# equalize_1.net
KiCad netlist of a schematic drawn in EAGLE
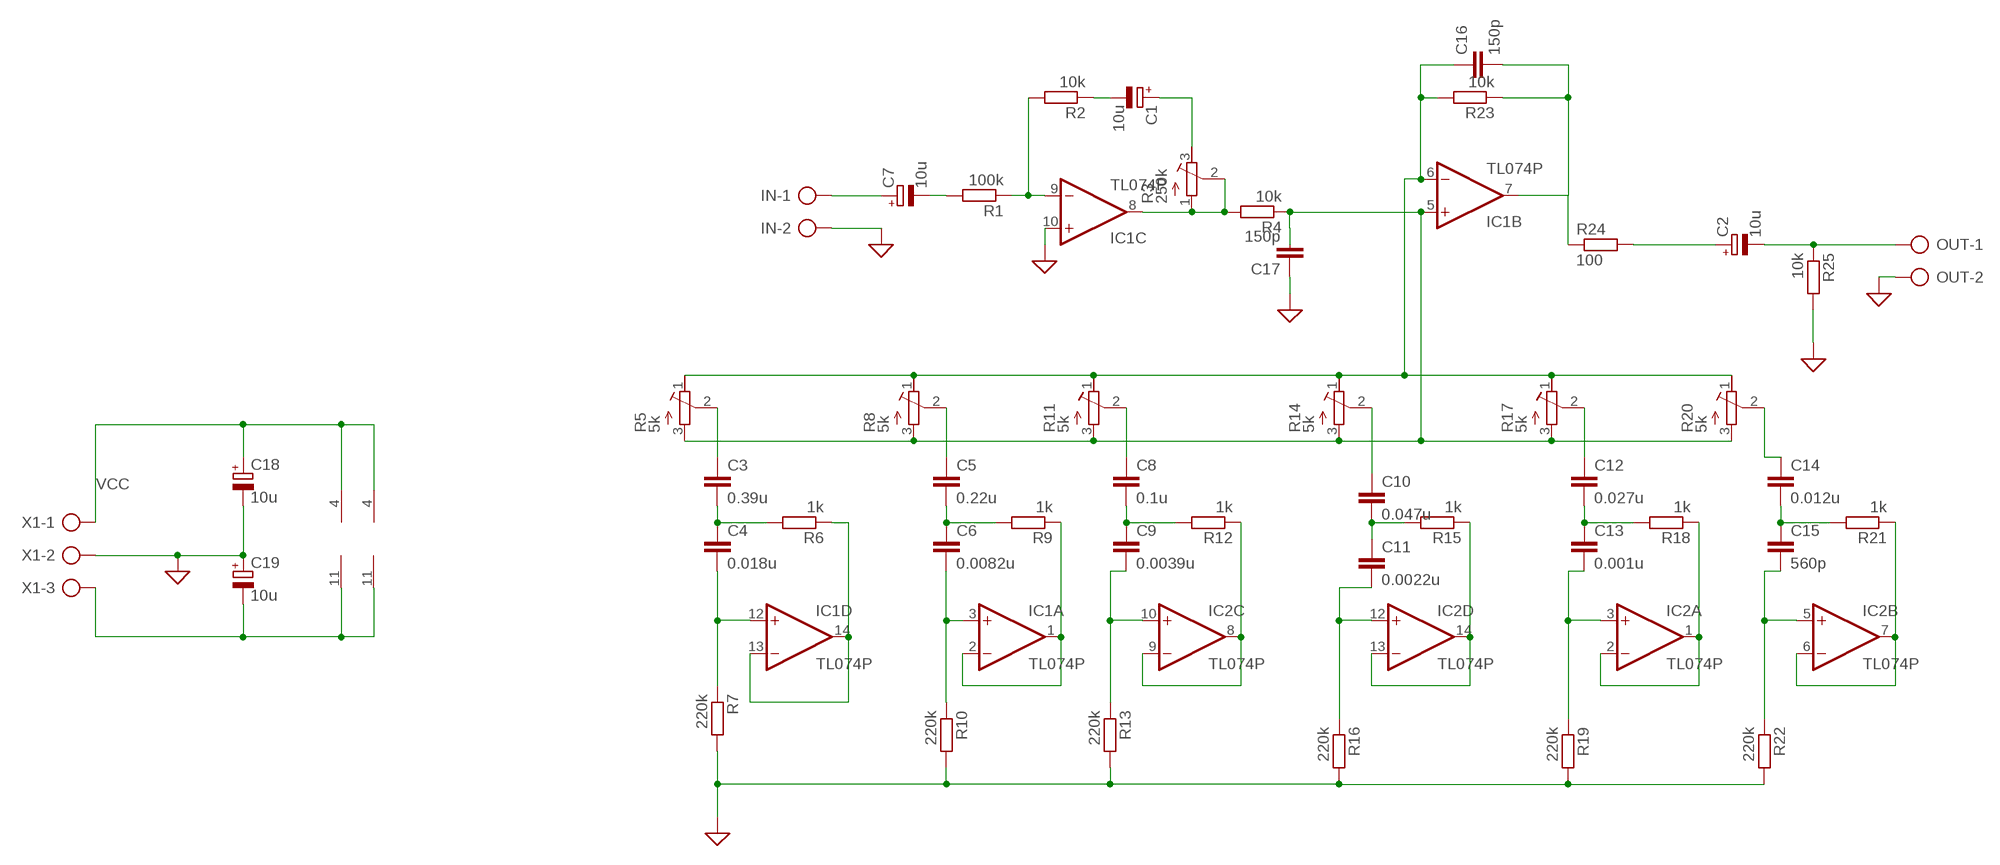
[diagram p0: schematic, sheet 1]

(export (version "E")
  (design (tool "Eeschema 10.0.6"))
  (components
    (comp (ref "C1")
      (value "10u")
      (footprint "eagle-import:E2,5-5")
      (libsource (lib "eagle-import") (part "CPOL-EUE2.5-5"))
    )
    (comp (ref "C2")
      (value "10u")
      (footprint "eagle-import:E2,5-5")
      (libsource (lib "eagle-import") (part "CPOL-EUE2.5-5"))
    )
    (comp (ref "C3")
      (value "0.39u")
      (footprint "eagle-import:C0603")
      (libsource (lib "eagle-import") (part "C-EUC0603"))
    )
    (comp (ref "C4")
      (value "0.018u")
      (footprint "eagle-import:C0603")
      (libsource (lib "eagle-import") (part "C-EUC0603"))
    )
    (comp (ref "C5")
      (value "0.22u")
      (footprint "eagle-import:C0603")
      (libsource (lib "eagle-import") (part "C-EUC0603"))
    )
    (comp (ref "C6")
      (value "0.0082u")
      (footprint "eagle-import:C0603")
      (libsource (lib "eagle-import") (part "C-EUC0603"))
    )
    (comp (ref "C7")
      (value "10u")
      (footprint "eagle-import:E2,5-5")
      (libsource (lib "eagle-import") (part "CPOL-EUE2.5-5"))
    )
    (comp (ref "C8")
      (value "0.1u")
      (footprint "eagle-import:C0603")
      (libsource (lib "eagle-import") (part "C-EUC0603"))
    )
    (comp (ref "C9")
      (value "0.0039u")
      (footprint "eagle-import:C0603")
      (libsource (lib "eagle-import") (part "C-EUC0603"))
    )
    (comp (ref "C10")
      (value "0.047u")
      (footprint "eagle-import:C0603")
      (libsource (lib "eagle-import") (part "C-EUC0603"))
    )
    (comp (ref "C11")
      (value "0.0022u")
      (footprint "eagle-import:C0603")
      (libsource (lib "eagle-import") (part "C-EUC0603"))
    )
    (comp (ref "C12")
      (value "0.027u")
      (footprint "eagle-import:C0603")
      (libsource (lib "eagle-import") (part "C-EUC0603"))
    )
    (comp (ref "C13")
      (value "0.001u")
      (footprint "eagle-import:C0603")
      (libsource (lib "eagle-import") (part "C-EUC0603"))
    )
    (comp (ref "C14")
      (value "0.012u")
      (footprint "eagle-import:C0603")
      (libsource (lib "eagle-import") (part "C-EUC0603"))
    )
    (comp (ref "C15")
      (value "560p")
      (footprint "eagle-import:C0603")
      (libsource (lib "eagle-import") (part "C-EUC0603"))
    )
    (comp (ref "C16")
      (value "150p")
      (footprint "eagle-import:C0603")
      (libsource (lib "eagle-import") (part "C-EUC0603"))
    )
    (comp (ref "C17")
      (value "150p")
      (footprint "eagle-import:C0603")
      (libsource (lib "eagle-import") (part "C-EUC0603"))
    )
    (comp (ref "C18")
      (value "10u")
      (footprint "eagle-import:E2,5-5")
      (libsource (lib "eagle-import") (part "CPOL-EUE2.5-5"))
    )
    (comp (ref "C19")
      (value "10u")
      (footprint "eagle-import:E2,5-5")
      (libsource (lib "eagle-import") (part "CPOL-EUE2.5-5"))
    )
    (comp (ref "IC1")
      (value "TL074P")
      (footprint "eagle-import:DIL14")
      (libsource (lib "eagle-import") (part "TL074P"))
    )
    (comp (ref "IC2")
      (value "TL074P")
      (footprint "eagle-import:DIL14")
      (libsource (lib "eagle-import") (part "TL074P"))
    )
    (comp (ref "IN")
      (value "AK500/2")
      (footprint "eagle-import:AK500_2")
      (libsource (lib "eagle-import") (part "AK500/2"))
    )
    (comp (ref "OUT")
      (value "AK500/2")
      (footprint "eagle-import:AK500_2")
      (libsource (lib "eagle-import") (part "AK500/2"))
    )
    (comp (ref "R1")
      (value "100k")
      (footprint "eagle-import:0207_7")
      (libsource (lib "eagle-import") (part "R-EU_0207/7"))
    )
    (comp (ref "R2")
      (value "10k")
      (footprint "eagle-import:0207_7")
      (libsource (lib "eagle-import") (part "R-EU_0207/7"))
    )
    (comp (ref "R3")
      (value "250k")
      (footprint "eagle-import:RTRIM3339P")
      (libsource (lib "eagle-import") (part "R-TRIMM3339P"))
    )
    (comp (ref "R4")
      (value "10k")
      (footprint "eagle-import:0207_7")
      (libsource (lib "eagle-import") (part "R-EU_0207/7"))
    )
    (comp (ref "R5")
      (value "5k")
      (footprint "eagle-import:RTRIMT93YA")
      (libsource (lib "eagle-import") (part "resistor_R-TRIMMT93YA"))
    )
    (comp (ref "R6")
      (value "1k")
      (footprint "eagle-import:0207_7")
      (libsource (lib "eagle-import") (part "R-EU_0207/7"))
    )
    (comp (ref "R7")
      (value "220k")
      (footprint "eagle-import:0207_7")
      (libsource (lib "eagle-import") (part "R-EU_0207/7"))
    )
    (comp (ref "R8")
      (value "5k")
      (footprint "eagle-import:RTRIMT93YA")
      (libsource (lib "eagle-import") (part "resistor_R-TRIMMT93YA"))
    )
    (comp (ref "R9")
      (value "1k")
      (footprint "eagle-import:0207_7")
      (libsource (lib "eagle-import") (part "R-EU_0207/7"))
    )
    (comp (ref "R10")
      (value "220k")
      (footprint "eagle-import:0207_7")
      (libsource (lib "eagle-import") (part "R-EU_0207/7"))
    )
    (comp (ref "R11")
      (value "5k")
      (footprint "eagle-import:RTRIMT93YA")
      (libsource (lib "eagle-import") (part "resistor_R-TRIMMT93YA"))
    )
    (comp (ref "R12")
      (value "1k")
      (footprint "eagle-import:0207_7")
      (libsource (lib "eagle-import") (part "R-EU_0207/7"))
    )
    (comp (ref "R13")
      (value "220k")
      (footprint "eagle-import:0207_7")
      (libsource (lib "eagle-import") (part "R-EU_0207/7"))
    )
    (comp (ref "R14")
      (value "5k")
      (footprint "eagle-import:RTRIMT93YA")
      (libsource (lib "eagle-import") (part "resistor_R-TRIMMT93YA"))
    )
    (comp (ref "R15")
      (value "1k")
      (footprint "eagle-import:0207_7")
      (libsource (lib "eagle-import") (part "R-EU_0207/7"))
    )
    (comp (ref "R16")
      (value "220k")
      (footprint "eagle-import:0207_7")
      (libsource (lib "eagle-import") (part "R-EU_0207/7"))
    )
    (comp (ref "R17")
      (value "5k")
      (footprint "eagle-import:RTRIMT93YA")
      (libsource (lib "eagle-import") (part "resistor_R-TRIMMT93YA"))
    )
    (comp (ref "R18")
      (value "1k")
      (footprint "eagle-import:0207_7")
      (libsource (lib "eagle-import") (part "R-EU_0207/7"))
    )
    (comp (ref "R19")
      (value "220k")
      (footprint "eagle-import:0207_7")
      (libsource (lib "eagle-import") (part "R-EU_0207/7"))
    )
    (comp (ref "R20")
      (value "5k")
      (footprint "eagle-import:RTRIMT93YA")
      (libsource (lib "eagle-import") (part "resistor_R-TRIMMT93YA"))
    )
    (comp (ref "R21")
      (value "1k")
      (footprint "eagle-import:0207_7")
      (libsource (lib "eagle-import") (part "R-EU_0207/7"))
    )
    (comp (ref "R22")
      (value "220k")
      (footprint "eagle-import:0207_7")
      (libsource (lib "eagle-import") (part "R-EU_0207/7"))
    )
    (comp (ref "R23")
      (value "10k")
      (footprint "eagle-import:0207_7")
      (libsource (lib "eagle-import") (part "R-EU_0207/7"))
    )
    (comp (ref "R24")
      (value "100")
      (footprint "eagle-import:0207_7")
      (libsource (lib "eagle-import") (part "R-EU_0207/7"))
    )
    (comp (ref "R25")
      (value "10k")
      (footprint "eagle-import:0207_7")
      (libsource (lib "eagle-import") (part "R-EU_0207/7"))
    )
    (comp (ref "X1")
      (value "AK500/3")
      (footprint "eagle-import:AK500_3")
      (libsource (lib "eagle-import") (part "AK500/3"))
    )
  )
  (nets
    (net (code "1") (name "/VCC") (class "Default")
      (node (ref "C18") (pin "+") (pinfunction "+_+") (pintype "passive"))
      (node (ref "IC1") (pin "4") (pinfunction "V+_4") (pintype "power_in"))
      (node (ref "IC2") (pin "4") (pinfunction "V+_4") (pintype "power_in"))
      (node (ref "X1") (pin "1") (pinfunction "KL_1") (pintype "passive"))
    )
    (net (code "2") (name "Net-(C1-Pad-)") (class "Default")
      (node (ref "C1") (pin "-") (pinfunction "-_-") (pintype "passive"))
      (node (ref "R2") (pin "1") (pinfunction "1_1") (pintype "passive"))
    )
    (net (code "3") (name "Net-(C2-Pad+)") (class "Default")
      (node (ref "C2") (pin "+") (pinfunction "+_+") (pintype "passive"))
      (node (ref "R24") (pin "2") (pinfunction "2_2") (pintype "passive"))
    )
    (net (code "4") (name "Net-(C3-Pad2)") (class "Default")
      (node (ref "C3") (pin "2") (pinfunction "2_2") (pintype "passive"))
      (node (ref "C4") (pin "1") (pinfunction "1_1") (pintype "passive"))
      (node (ref "R6") (pin "2") (pinfunction "2_2") (pintype "passive"))
    )
    (net (code "5") (name "Net-(C5-Pad2)") (class "Default")
      (node (ref "C5") (pin "2") (pinfunction "2_2") (pintype "passive"))
      (node (ref "C6") (pin "1") (pinfunction "1_1") (pintype "passive"))
      (node (ref "R9") (pin "2") (pinfunction "2_2") (pintype "passive"))
    )
    (net (code "6") (name "Net-(C7-Pad-)") (class "Default")
      (node (ref "C7") (pin "-") (pinfunction "-_-") (pintype "passive"))
      (node (ref "R1") (pin "2") (pinfunction "2_2") (pintype "passive"))
    )
    (net (code "7") (name "Net-(C8-Pad2)") (class "Default")
      (node (ref "C8") (pin "2") (pinfunction "2_2") (pintype "passive"))
      (node (ref "C9") (pin "1") (pinfunction "1_1") (pintype "passive"))
      (node (ref "R12") (pin "2") (pinfunction "2_2") (pintype "passive"))
    )
    (net (code "8") (name "Net-(C10-Pad2)") (class "Default")
      (node (ref "C10") (pin "2") (pinfunction "2_2") (pintype "passive"))
      (node (ref "C11") (pin "1") (pinfunction "1_1") (pintype "passive"))
      (node (ref "R15") (pin "2") (pinfunction "2_2") (pintype "passive"))
    )
    (net (code "9") (name "Net-(C12-Pad2)") (class "Default")
      (node (ref "C12") (pin "2") (pinfunction "2_2") (pintype "passive"))
      (node (ref "C13") (pin "1") (pinfunction "1_1") (pintype "passive"))
      (node (ref "R18") (pin "2") (pinfunction "2_2") (pintype "passive"))
    )
    (net (code "10") (name "Net-(C14-Pad2)") (class "Default")
      (node (ref "C14") (pin "2") (pinfunction "2_2") (pintype "passive"))
      (node (ref "C15") (pin "1") (pinfunction "1_1") (pintype "passive"))
      (node (ref "R21") (pin "2") (pinfunction "2_2") (pintype "passive"))
    )
    (net (code "11") (name "Net-(IC1A-+IN)") (class "Default")
      (node (ref "C6") (pin "2") (pinfunction "2_2") (pintype "passive"))
      (node (ref "IC1") (pin "3") (pinfunction "+IN_3") (pintype "input"))
      (node (ref "R10") (pin "1") (pinfunction "1_1") (pintype "passive"))
    )
    (net (code "12") (name "Net-(IC1A--IN)") (class "Default")
      (node (ref "IC1") (pin "1") (pinfunction "OUT_1") (pintype "output"))
      (node (ref "IC1") (pin "2") (pinfunction "-IN_2") (pintype "input"))
      (node (ref "R9") (pin "1") (pinfunction "1_1") (pintype "passive"))
    )
    (net (code "13") (name "Net-(IC1B-+IN)") (class "Default")
      (node (ref "C17") (pin "2") (pinfunction "2_2") (pintype "passive"))
      (node (ref "IC1") (pin "5") (pinfunction "+IN_5") (pintype "input"))
      (node (ref "R11") (pin "3") (pinfunction "A_3") (pintype "passive"))
      (node (ref "R14") (pin "3") (pinfunction "A_3") (pintype "passive"))
      (node (ref "R17") (pin "3") (pinfunction "A_3") (pintype "passive"))
      (node (ref "R20") (pin "3") (pinfunction "A_3") (pintype "passive"))
      (node (ref "R4") (pin "1") (pinfunction "1_1") (pintype "passive"))
      (node (ref "R5") (pin "3") (pinfunction "A_3") (pintype "passive"))
      (node (ref "R8") (pin "3") (pinfunction "A_3") (pintype "passive"))
    )
    (net (code "14") (name "Net-(IC1B--IN)") (class "Default")
      (node (ref "C16") (pin "1") (pinfunction "1_1") (pintype "passive"))
      (node (ref "IC1") (pin "6") (pinfunction "-IN_6") (pintype "input"))
      (node (ref "R11") (pin "1") (pinfunction "E_1") (pintype "passive"))
      (node (ref "R14") (pin "1") (pinfunction "E_1") (pintype "passive"))
      (node (ref "R17") (pin "1") (pinfunction "E_1") (pintype "passive"))
      (node (ref "R20") (pin "1") (pinfunction "E_1") (pintype "passive"))
      (node (ref "R23") (pin "2") (pinfunction "2_2") (pintype "passive"))
      (node (ref "R5") (pin "1") (pinfunction "E_1") (pintype "passive"))
      (node (ref "R8") (pin "1") (pinfunction "E_1") (pintype "passive"))
    )
    (net (code "15") (name "Net-(IC1B-OUT)") (class "Default")
      (node (ref "C16") (pin "2") (pinfunction "2_2") (pintype "passive"))
      (node (ref "IC1") (pin "7") (pinfunction "OUT_7") (pintype "output"))
      (node (ref "R23") (pin "1") (pinfunction "1_1") (pintype "passive"))
      (node (ref "R24") (pin "1") (pinfunction "1_1") (pintype "passive"))
    )
    (net (code "16") (name "Net-(IC1C--IN)") (class "Default")
      (node (ref "IC1") (pin "9") (pinfunction "-IN_9") (pintype "input"))
      (node (ref "R1") (pin "1") (pinfunction "1_1") (pintype "passive"))
      (node (ref "R2") (pin "2") (pinfunction "2_2") (pintype "passive"))
    )
    (net (code "17") (name "Net-(IC1C-OUT)") (class "Default")
      (node (ref "IC1") (pin "8") (pinfunction "OUT_8") (pintype "output"))
      (node (ref "R3") (pin "1") (pinfunction "A_1") (pintype "passive"))
      (node (ref "R3") (pin "2") (pinfunction "S_2") (pintype "passive"))
      (node (ref "R4") (pin "2") (pinfunction "2_2") (pintype "passive"))
    )
    (net (code "18") (name "Net-(IC1D-+IN)") (class "Default")
      (node (ref "C4") (pin "2") (pinfunction "2_2") (pintype "passive"))
      (node (ref "IC1") (pin "12") (pinfunction "+IN_12") (pintype "input"))
      (node (ref "R7") (pin "1") (pinfunction "1_1") (pintype "passive"))
    )
    (net (code "19") (name "Net-(IC1D--IN)") (class "Default")
      (node (ref "IC1") (pin "13") (pinfunction "-IN_13") (pintype "input"))
      (node (ref "IC1") (pin "14") (pinfunction "OUT_14") (pintype "output"))
      (node (ref "R6") (pin "1") (pinfunction "1_1") (pintype "passive"))
    )
    (net (code "20") (name "Net-(IC1E-V-)") (class "Default")
      (node (ref "C19") (pin "-") (pinfunction "-_-") (pintype "passive"))
      (node (ref "IC1") (pin "11") (pinfunction "V-_11") (pintype "power_in"))
      (node (ref "IC2") (pin "11") (pinfunction "V-_11") (pintype "power_in"))
      (node (ref "X1") (pin "3") (pinfunction "KL_3") (pintype "passive"))
    )
    (net (code "21") (name "Net-(IC2A-+IN)") (class "Default")
      (node (ref "C13") (pin "2") (pinfunction "2_2") (pintype "passive"))
      (node (ref "IC2") (pin "3") (pinfunction "+IN_3") (pintype "input"))
      (node (ref "R19") (pin "1") (pinfunction "1_1") (pintype "passive"))
    )
    (net (code "22") (name "Net-(IC2A--IN)") (class "Default")
      (node (ref "IC2") (pin "1") (pinfunction "OUT_1") (pintype "output"))
      (node (ref "IC2") (pin "2") (pinfunction "-IN_2") (pintype "input"))
      (node (ref "R18") (pin "1") (pinfunction "1_1") (pintype "passive"))
    )
    (net (code "23") (name "Net-(IC2B-+IN)") (class "Default")
      (node (ref "C15") (pin "2") (pinfunction "2_2") (pintype "passive"))
      (node (ref "IC2") (pin "5") (pinfunction "+IN_5") (pintype "input"))
      (node (ref "R22") (pin "1") (pinfunction "1_1") (pintype "passive"))
    )
    (net (code "24") (name "Net-(IC2B--IN)") (class "Default")
      (node (ref "IC2") (pin "6") (pinfunction "-IN_6") (pintype "input"))
      (node (ref "IC2") (pin "7") (pinfunction "OUT_7") (pintype "output"))
      (node (ref "R21") (pin "1") (pinfunction "1_1") (pintype "passive"))
    )
    (net (code "25") (name "Net-(IC2C-+IN)") (class "Default")
      (node (ref "C9") (pin "2") (pinfunction "2_2") (pintype "passive"))
      (node (ref "IC2") (pin "10") (pinfunction "+IN_10") (pintype "input"))
      (node (ref "R13") (pin "1") (pinfunction "1_1") (pintype "passive"))
    )
    (net (code "26") (name "Net-(IC2C--IN)") (class "Default")
      (node (ref "IC2") (pin "8") (pinfunction "OUT_8") (pintype "output"))
      (node (ref "IC2") (pin "9") (pinfunction "-IN_9") (pintype "input"))
      (node (ref "R12") (pin "1") (pinfunction "1_1") (pintype "passive"))
    )
    (net (code "27") (name "Net-(IC2D-+IN)") (class "Default")
      (node (ref "C11") (pin "2") (pinfunction "2_2") (pintype "passive"))
      (node (ref "IC2") (pin "12") (pinfunction "+IN_12") (pintype "input"))
      (node (ref "R16") (pin "1") (pinfunction "1_1") (pintype "passive"))
    )
    (net (code "28") (name "Net-(IC2D--IN)") (class "Default")
      (node (ref "IC2") (pin "13") (pinfunction "-IN_13") (pintype "input"))
      (node (ref "IC2") (pin "14") (pinfunction "OUT_14") (pintype "output"))
      (node (ref "R15") (pin "1") (pinfunction "1_1") (pintype "passive"))
    )
    (net (code "29") (name "Net-(INA-KL)") (class "Default")
      (node (ref "C7") (pin "+") (pinfunction "+_+") (pintype "passive"))
      (node (ref "IN") (pin "1") (pinfunction "KL_1") (pintype "passive"))
    )
    (net (code "30") (name "Net-(OUTA-KL)") (class "Default")
      (node (ref "C2") (pin "-") (pinfunction "-_-") (pintype "passive"))
      (node (ref "OUT") (pin "1") (pinfunction "KL_1") (pintype "passive"))
      (node (ref "R25") (pin "1") (pinfunction "1_1") (pintype "passive"))
    )
    (net (code "31") (name "Net-(R3-E)") (class "Default")
      (node (ref "C1") (pin "+") (pinfunction "+_+") (pintype "passive"))
      (node (ref "R3") (pin "3") (pinfunction "E_3") (pintype "passive"))
    )
    (net (code "32") (name "Net-(R5-S)") (class "Default")
      (node (ref "C3") (pin "1") (pinfunction "1_1") (pintype "passive"))
      (node (ref "R5") (pin "2") (pinfunction "S_2") (pintype "passive"))
    )
    (net (code "33") (name "Net-(R8-S)") (class "Default")
      (node (ref "C5") (pin "1") (pinfunction "1_1") (pintype "passive"))
      (node (ref "R8") (pin "2") (pinfunction "S_2") (pintype "passive"))
    )
    (net (code "34") (name "Net-(R11-S)") (class "Default")
      (node (ref "C8") (pin "1") (pinfunction "1_1") (pintype "passive"))
      (node (ref "R11") (pin "2") (pinfunction "S_2") (pintype "passive"))
    )
    (net (code "35") (name "Net-(R14-S)") (class "Default")
      (node (ref "C10") (pin "1") (pinfunction "1_1") (pintype "passive"))
      (node (ref "R14") (pin "2") (pinfunction "S_2") (pintype "passive"))
    )
    (net (code "36") (name "Net-(R17-S)") (class "Default")
      (node (ref "C12") (pin "1") (pinfunction "1_1") (pintype "passive"))
      (node (ref "R17") (pin "2") (pinfunction "S_2") (pintype "passive"))
    )
    (net (code "37") (name "Net-(R20-S)") (class "Default")
      (node (ref "C14") (pin "1") (pinfunction "1_1") (pintype "passive"))
      (node (ref "R20") (pin "2") (pinfunction "S_2") (pintype "passive"))
    )
    (net (code "38") (name "SUP") (class "Default")
      (node (ref "C17") (pin "1") (pinfunction "1_1") (pintype "passive"))
      (node (ref "C18") (pin "-") (pinfunction "-_-") (pintype "passive"))
      (node (ref "C19") (pin "+") (pinfunction "+_+") (pintype "passive"))
      (node (ref "IC1") (pin "10") (pinfunction "+IN_10") (pintype "input"))
      (node (ref "IN") (pin "2") (pinfunction "KL_2") (pintype "passive"))
      (node (ref "OUT") (pin "2") (pinfunction "KL_2") (pintype "passive"))
      (node (ref "R10") (pin "2") (pinfunction "2_2") (pintype "passive"))
      (node (ref "R13") (pin "2") (pinfunction "2_2") (pintype "passive"))
      (node (ref "R16") (pin "2") (pinfunction "2_2") (pintype "passive"))
      (node (ref "R19") (pin "2") (pinfunction "2_2") (pintype "passive"))
      (node (ref "R22") (pin "2") (pinfunction "2_2") (pintype "passive"))
      (node (ref "R25") (pin "2") (pinfunction "2_2") (pintype "passive"))
      (node (ref "R7") (pin "2") (pinfunction "2_2") (pintype "passive"))
      (node (ref "X1") (pin "2") (pinfunction "KL_2") (pintype "passive"))
    )
  )
)
